# Display_Indicators.net
KiCad netlist of a schematic drawn in Altium Designer
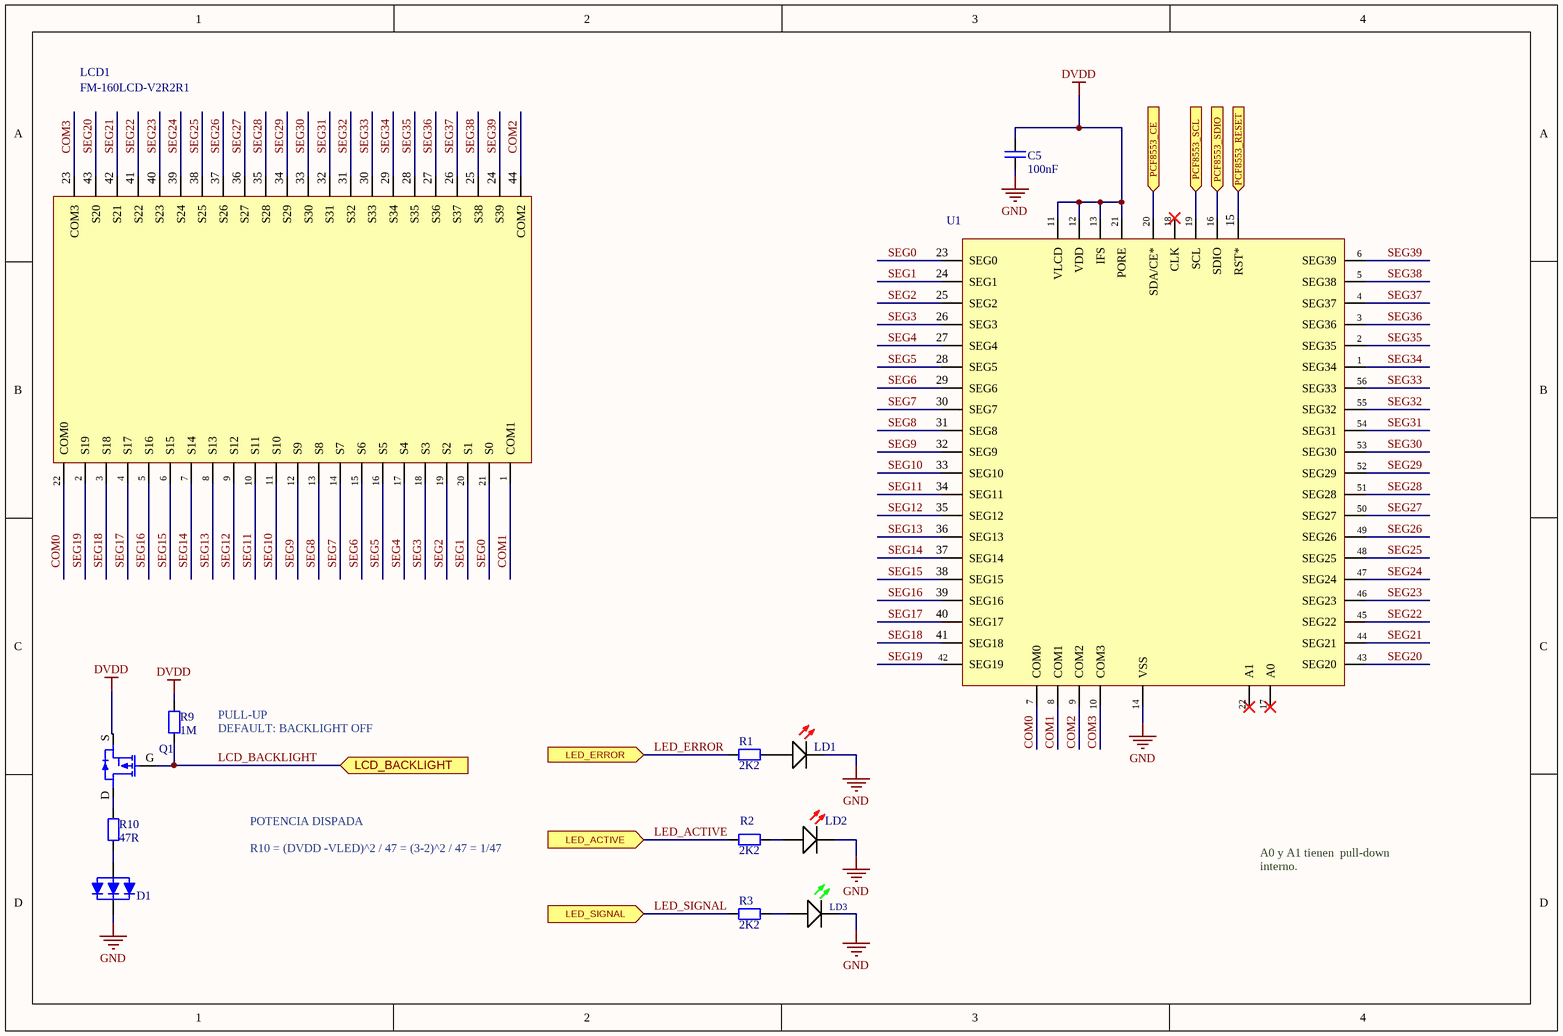
[diagram p0: Display_Indicators.SchDoc]

(export (version "E")
  (design (tool "Eeschema 10.0.6"))
  (components
    (comp (ref "C5")
      (value "100nF")
      (footprint "CAP_SM0603_YAGEOCC2_N")
      (description "CAP 100nF SM0603 X7R 50V YAGEO CC2")
      (fields
        (field (name "MANUFACTURER") "Yageo")
        (field (name "MANUFACTURER PART NUMBER") "CC0603KRX7R9BB104")
      )
      (libsource (lib "yageo") (part "CC0603KRX7R9BB104"))
    )
    (comp (ref "D1")
      (value "BACKLIGHT")
      (footprint "BACKLIGHT_2")
      (description "IF=45mA;VF=3V")
      (fields
        (field (name "MANUFACTURER") "FLOWMEET")
        (field (name "MANUFACTURER PART NUMBER") "FM-160-BACKLIGHT")
      )
      (libsource (lib "flowmeet") (part "FM-160-BACKLIGHT"))
    )
    (comp (ref "LCD1")
      (value "FM-160LCD-V2R2R1")
      (footprint "FMC-160LCD V2")
      (fields (field (name "MANUFACTURER") "FLOWMEET"))
      (libsource (lib "flowmeet") (part "FM-160LCD-V2R2R1"))
    )
    (comp (ref "LD1")
      (value "RED")
      (footprint "LED 0805")
      (fields
        (field (name "MANUFACTURER") "Everlight Elec")
        (field (name "MANUFACTURER PART NUMBER") "17-21SURC/S530-A2/TR8")
      )
      (libsource (lib "flowmeet") (part "17-21SURC/S530-A2/TR8"))
    )
    (comp (ref "LD2")
      (value "RED")
      (footprint "LED 0805")
      (fields
        (field (name "MANUFACTURER") "Everlight Elec")
        (field (name "MANUFACTURER PART NUMBER") "17-21SURC/S530-A2/TR8")
      )
      (libsource (lib "flowmeet") (part "17-21SURC/S530-A2/TR8"))
    )
    (comp (ref "LD3")
      (value "GREEN")
      (footprint "LED 0805")
      (fields
        (field (name "MANUFACTURER") "Everlight Elec")
        (field (name "MANUFACTURER PART NUMBER") "21SYGC/S530-E2/TR8")
      )
      (libsource (lib "flowmeet") (part "17-21SYGC/S530-E2/TR8"))
    )
    (comp (ref "Q1")
      (value "DMG3401LSN-7")
      (footprint "DMG3401LSN-7")
      (description "P-CHANNEL ENHANCEMENT MODE MOSFET\r\nRDS(ON) = 85mΩ @ VGS = -2.5V -> ID -2.7A\r\nV(BR)DDS 30V")
      (fields (field (name "MANUFACTURER") "Diodes Incorporated"))
      (libsource (lib "mosfet") (part "DMG3401LSN-7"))
    )
    (comp (ref "R1")
      (value "2K2")
      (footprint "RES_SM0603_YAGEORC_N")
      (description "RES 2K2 SM0603 YAGEO RC_L")
      (fields
        (field (name "MANUFACTURER") "Yageo")
        (field (name "MANUFACTURER PART NUMBER") "RC0603FR-072K2L")
      )
      (libsource (lib "yageo") (part "RC0603FR-072K2L"))
    )
    (comp (ref "R2")
      (value "2K2")
      (footprint "RES_SM0603_YAGEORC_N")
      (description "RES 2K2 SM0603 YAGEO RC_L")
      (fields
        (field (name "MANUFACTURER") "Yageo")
        (field (name "MANUFACTURER PART NUMBER") "RC0603FR-072K2L")
      )
      (libsource (lib "yageo") (part "RC0603FR-072K2L"))
    )
    (comp (ref "R3")
      (value "2K2")
      (footprint "RES_SM0603_YAGEORC_N")
      (description "RES 2K2 SM0603 YAGEO RC_L")
      (fields
        (field (name "MANUFACTURER") "Yageo")
        (field (name "MANUFACTURER PART NUMBER") "RC0603FR-072K2L")
      )
      (libsource (lib "yageo") (part "RC0603FR-072K2L"))
    )
    (comp (ref "R9")
      (value "1M")
      (footprint "RES_SM0603_YAGEORC_N")
      (description "RES 1M SM0603 YAGEO RC_L")
      (fields
        (field (name "MANUFACTURER") "Yageo")
        (field (name "MANUFACTURER PART NUMBER") "RC0603FR-071ML")
      )
      (libsource (lib "yageo") (part "RC0603FR-071ML"))
    )
    (comp (ref "R10")
      (value "47R")
      (footprint "RES_SM0603_YAGEORC_N")
      (description "RES 47R SM0603 YAGEO RC_L")
      (fields
        (field (name "MANUFACTURER") "Yageo")
        (field (name "MANUFACTURER PART NUMBER") "RC0603FR-0747RL")
      )
      (libsource (lib "yageo") (part "RC0603FR-0747RL"))
    )
    (comp (ref "U1")
      (value "~")
      (footprint "LCD DRIVER - TSSOP56")
      (description "40 × 4 LCD SEGMENT DRIVER")
      (fields (field (name "MANUFACTURER") "NXP") (field (name "MANUFACTURER PART NUMBER") "PCF8553DTT/AY"))
      (libsource (lib "flowmeet") (part "PCF8553DTT/AY"))
    )
  )
  (nets
    (net (code "1") (name "/COM0") (class "Default")
      (node (ref "LCD1") (pin "22") (pinfunction "COM0_22") (pintype "passive"))
      (node (ref "U1") (pin "7") (pinfunction "COM0_7") (pintype "passive"))
    )
    (net (code "2") (name "/COM1") (class "Default")
      (node (ref "LCD1") (pin "1") (pinfunction "COM1_1") (pintype "passive"))
      (node (ref "U1") (pin "8") (pinfunction "COM1_8") (pintype "passive"))
    )
    (net (code "3") (name "/COM2") (class "Default")
      (node (ref "LCD1") (pin "44") (pinfunction "COM2_44") (pintype "passive"))
      (node (ref "U1") (pin "9") (pinfunction "COM2_9") (pintype "passive"))
    )
    (net (code "4") (name "/COM3") (class "Default")
      (node (ref "LCD1") (pin "23") (pinfunction "COM3_23") (pintype "passive"))
      (node (ref "U1") (pin "10") (pinfunction "COM3_10") (pintype "passive"))
    )
    (net (code "5") (name "/LCD_BACKLIGHT") (class "Default")
      (node (ref "Q1") (pin "G") (pinfunction "G_G") (pintype "passive"))
      (node (ref "R9") (pin "1") (pintype "passive"))
    )
    (net (code "6") (name "/LED_ACTIVE") (class "Default") (node (ref "R2") (pin "1") (pintype "passive")))
    (net (code "7") (name "/LED_ERROR") (class "Default") (node (ref "R1") (pin "1") (pintype "passive")))
    (net (code "8") (name "/LED_SIGNAL") (class "Default") (node (ref "R3") (pin "1") (pintype "passive")))
    (net (code "9") (name "/PCF8553_CE") (class "Default")
      (node (ref "U1") (pin "20") (pinfunction "SDA/CE*_20") (pintype "passive"))
    )
    (net (code "10") (name "/PCF8553_RESET") (class "Default")
      (node (ref "U1") (pin "15") (pinfunction "RST*_15") (pintype "passive"))
    )
    (net (code "11") (name "/PCF8553_SCL") (class "Default")
      (node (ref "U1") (pin "19") (pinfunction "SCL_19") (pintype "passive"))
    )
    (net (code "12") (name "/PCF8553_SDIO") (class "Default")
      (node (ref "U1") (pin "16") (pinfunction "SDIO_16") (pintype "passive"))
    )
    (net (code "13") (name "/SEG0") (class "Default")
      (node (ref "LCD1") (pin "21") (pinfunction "S0_21") (pintype "passive"))
      (node (ref "U1") (pin "23") (pinfunction "SEG0_23") (pintype "passive"))
    )
    (net (code "14") (name "/SEG1") (class "Default")
      (node (ref "LCD1") (pin "20") (pinfunction "S1_20") (pintype "passive"))
      (node (ref "U1") (pin "24") (pinfunction "SEG1_24") (pintype "passive"))
    )
    (net (code "15") (name "/SEG2") (class "Default")
      (node (ref "LCD1") (pin "19") (pinfunction "S2_19") (pintype "passive"))
      (node (ref "U1") (pin "25") (pinfunction "SEG2_25") (pintype "passive"))
    )
    (net (code "16") (name "/SEG3") (class "Default")
      (node (ref "LCD1") (pin "18") (pinfunction "S3_18") (pintype "passive"))
      (node (ref "U1") (pin "26") (pinfunction "SEG3_26") (pintype "passive"))
    )
    (net (code "17") (name "/SEG4") (class "Default")
      (node (ref "LCD1") (pin "17") (pinfunction "S4_17") (pintype "passive"))
      (node (ref "U1") (pin "27") (pinfunction "SEG4_27") (pintype "passive"))
    )
    (net (code "18") (name "/SEG5") (class "Default")
      (node (ref "LCD1") (pin "16") (pinfunction "S5_16") (pintype "passive"))
      (node (ref "U1") (pin "28") (pinfunction "SEG5_28") (pintype "passive"))
    )
    (net (code "19") (name "/SEG6") (class "Default")
      (node (ref "LCD1") (pin "15") (pinfunction "S6_15") (pintype "passive"))
      (node (ref "U1") (pin "29") (pinfunction "SEG6_29") (pintype "passive"))
    )
    (net (code "20") (name "/SEG7") (class "Default")
      (node (ref "LCD1") (pin "14") (pinfunction "S7_14") (pintype "passive"))
      (node (ref "U1") (pin "30") (pinfunction "SEG7_30") (pintype "passive"))
    )
    (net (code "21") (name "/SEG8") (class "Default")
      (node (ref "LCD1") (pin "13") (pinfunction "S8_13") (pintype "passive"))
      (node (ref "U1") (pin "31") (pinfunction "SEG8_31") (pintype "passive"))
    )
    (net (code "22") (name "/SEG9") (class "Default")
      (node (ref "LCD1") (pin "12") (pinfunction "S9_12") (pintype "passive"))
      (node (ref "U1") (pin "32") (pinfunction "SEG9_32") (pintype "passive"))
    )
    (net (code "23") (name "/SEG10") (class "Default")
      (node (ref "LCD1") (pin "11") (pinfunction "S10_11") (pintype "passive"))
      (node (ref "U1") (pin "33") (pinfunction "SEG10_33") (pintype "passive"))
    )
    (net (code "24") (name "/SEG11") (class "Default")
      (node (ref "LCD1") (pin "10") (pinfunction "S11_10") (pintype "passive"))
      (node (ref "U1") (pin "34") (pinfunction "SEG11_34") (pintype "passive"))
    )
    (net (code "25") (name "/SEG12") (class "Default")
      (node (ref "LCD1") (pin "9") (pinfunction "S12_9") (pintype "passive"))
      (node (ref "U1") (pin "35") (pinfunction "SEG12_35") (pintype "passive"))
    )
    (net (code "26") (name "/SEG13") (class "Default")
      (node (ref "LCD1") (pin "8") (pinfunction "S13_8") (pintype "passive"))
      (node (ref "U1") (pin "36") (pinfunction "SEG13_36") (pintype "passive"))
    )
    (net (code "27") (name "/SEG14") (class "Default")
      (node (ref "LCD1") (pin "7") (pinfunction "S14_7") (pintype "passive"))
      (node (ref "U1") (pin "37") (pinfunction "SEG14_37") (pintype "passive"))
    )
    (net (code "28") (name "/SEG15") (class "Default")
      (node (ref "LCD1") (pin "6") (pinfunction "S15_6") (pintype "passive"))
      (node (ref "U1") (pin "38") (pinfunction "SEG15_38") (pintype "passive"))
    )
    (net (code "29") (name "/SEG16") (class "Default")
      (node (ref "LCD1") (pin "5") (pinfunction "S16_5") (pintype "passive"))
      (node (ref "U1") (pin "39") (pinfunction "SEG16_39") (pintype "passive"))
    )
    (net (code "30") (name "/SEG17") (class "Default")
      (node (ref "LCD1") (pin "4") (pinfunction "S17_4") (pintype "passive"))
      (node (ref "U1") (pin "40") (pinfunction "SEG17_40") (pintype "passive"))
    )
    (net (code "31") (name "/SEG18") (class "Default")
      (node (ref "LCD1") (pin "3") (pinfunction "S18_3") (pintype "passive"))
      (node (ref "U1") (pin "41") (pinfunction "SEG18_41") (pintype "passive"))
    )
    (net (code "32") (name "/SEG19") (class "Default")
      (node (ref "LCD1") (pin "2") (pinfunction "S19_2") (pintype "passive"))
      (node (ref "U1") (pin "42") (pinfunction "SEG19_42") (pintype "passive"))
    )
    (net (code "33") (name "/SEG20") (class "Default")
      (node (ref "LCD1") (pin "43") (pinfunction "S20_43") (pintype "passive"))
      (node (ref "U1") (pin "43") (pinfunction "SEG20_43") (pintype "passive"))
    )
    (net (code "34") (name "/SEG21") (class "Default")
      (node (ref "LCD1") (pin "42") (pinfunction "S21_42") (pintype "passive"))
      (node (ref "U1") (pin "44") (pinfunction "SEG21_44") (pintype "passive"))
    )
    (net (code "35") (name "/SEG22") (class "Default")
      (node (ref "LCD1") (pin "41") (pinfunction "S22_41") (pintype "passive"))
      (node (ref "U1") (pin "45") (pinfunction "SEG22_45") (pintype "passive"))
    )
    (net (code "36") (name "/SEG23") (class "Default")
      (node (ref "LCD1") (pin "40") (pinfunction "S23_40") (pintype "passive"))
      (node (ref "U1") (pin "46") (pinfunction "SEG23_46") (pintype "passive"))
    )
    (net (code "37") (name "/SEG24") (class "Default")
      (node (ref "LCD1") (pin "39") (pinfunction "S24_39") (pintype "passive"))
      (node (ref "U1") (pin "47") (pinfunction "SEG24_47") (pintype "passive"))
    )
    (net (code "38") (name "/SEG25") (class "Default")
      (node (ref "LCD1") (pin "38") (pinfunction "S25_38") (pintype "passive"))
      (node (ref "U1") (pin "48") (pinfunction "SEG25_48") (pintype "passive"))
    )
    (net (code "39") (name "/SEG26") (class "Default")
      (node (ref "LCD1") (pin "37") (pinfunction "S26_37") (pintype "passive"))
      (node (ref "U1") (pin "49") (pinfunction "SEG26_49") (pintype "passive"))
    )
    (net (code "40") (name "/SEG27") (class "Default")
      (node (ref "LCD1") (pin "36") (pinfunction "S27_36") (pintype "passive"))
      (node (ref "U1") (pin "50") (pinfunction "SEG27_50") (pintype "passive"))
    )
    (net (code "41") (name "/SEG28") (class "Default")
      (node (ref "LCD1") (pin "35") (pinfunction "S28_35") (pintype "passive"))
      (node (ref "U1") (pin "51") (pinfunction "SEG28_51") (pintype "passive"))
    )
    (net (code "42") (name "/SEG29") (class "Default")
      (node (ref "LCD1") (pin "34") (pinfunction "S29_34") (pintype "passive"))
      (node (ref "U1") (pin "52") (pinfunction "SEG29_52") (pintype "passive"))
    )
    (net (code "43") (name "/SEG30") (class "Default")
      (node (ref "LCD1") (pin "33") (pinfunction "S30_33") (pintype "passive"))
      (node (ref "U1") (pin "53") (pinfunction "SEG30_53") (pintype "passive"))
    )
    (net (code "44") (name "/SEG31") (class "Default")
      (node (ref "LCD1") (pin "32") (pinfunction "S31_32") (pintype "passive"))
      (node (ref "U1") (pin "54") (pinfunction "SEG31_54") (pintype "passive"))
    )
    (net (code "45") (name "/SEG32") (class "Default")
      (node (ref "LCD1") (pin "31") (pinfunction "S32_31") (pintype "passive"))
      (node (ref "U1") (pin "55") (pinfunction "SEG32_55") (pintype "passive"))
    )
    (net (code "46") (name "/SEG33") (class "Default")
      (node (ref "LCD1") (pin "30") (pinfunction "S33_30") (pintype "passive"))
      (node (ref "U1") (pin "56") (pinfunction "SEG33_56") (pintype "passive"))
    )
    (net (code "47") (name "/SEG34") (class "Default")
      (node (ref "LCD1") (pin "29") (pinfunction "S34_29") (pintype "passive"))
      (node (ref "U1") (pin "1") (pinfunction "SEG34_1") (pintype "passive"))
    )
    (net (code "48") (name "/SEG35") (class "Default")
      (node (ref "LCD1") (pin "28") (pinfunction "S35_28") (pintype "passive"))
      (node (ref "U1") (pin "2") (pinfunction "SEG35_2") (pintype "passive"))
    )
    (net (code "49") (name "/SEG36") (class "Default")
      (node (ref "LCD1") (pin "27") (pinfunction "S36_27") (pintype "passive"))
      (node (ref "U1") (pin "3") (pinfunction "SEG36_3") (pintype "passive"))
    )
    (net (code "50") (name "/SEG37") (class "Default")
      (node (ref "LCD1") (pin "26") (pinfunction "S37_26") (pintype "passive"))
      (node (ref "U1") (pin "4") (pinfunction "SEG37_4") (pintype "passive"))
    )
    (net (code "51") (name "/SEG38") (class "Default")
      (node (ref "LCD1") (pin "25") (pinfunction "S38_25") (pintype "passive"))
      (node (ref "U1") (pin "5") (pinfunction "SEG38_5") (pintype "passive"))
    )
    (net (code "52") (name "/SEG39") (class "Default")
      (node (ref "LCD1") (pin "24") (pinfunction "S39_24") (pintype "passive"))
      (node (ref "U1") (pin "6") (pinfunction "SEG39_6") (pintype "passive"))
    )
    (net (code "53") (name "DVDD") (class "Default")
      (node (ref "C5") (pin "1") (pintype "passive"))
      (node (ref "Q1") (pin "S") (pinfunction "S_S") (pintype "passive"))
      (node (ref "R9") (pin "2") (pintype "passive"))
      (node (ref "U1") (pin "11") (pinfunction "VLCD_11") (pintype "passive"))
      (node (ref "U1") (pin "12") (pinfunction "VDD_12") (pintype "passive"))
      (node (ref "U1") (pin "13") (pinfunction "IFS_13") (pintype "passive"))
      (node (ref "U1") (pin "21") (pinfunction "PORE_21") (pintype "passive"))
    )
    (net (code "54") (name "GND") (class "Default")
      (node (ref "C5") (pin "2") (pintype "passive"))
      (node (ref "D1") (pin "2") (pinfunction "0_2") (pintype "passive"))
      (node (ref "LD1") (pin "K") (pinfunction "K_K") (pintype "passive"))
      (node (ref "LD2") (pin "K") (pinfunction "K_K") (pintype "passive"))
      (node (ref "LD3") (pin "K") (pinfunction "K_K") (pintype "passive"))
      (node (ref "U1") (pin "14") (pinfunction "VSS_14") (pintype "passive"))
    )
    (net (code "55") (name "Net-(D1-Pad1)") (class "Default")
      (node (ref "D1") (pin "1") (pinfunction "1_1") (pintype "passive"))
      (node (ref "R10") (pin "1") (pintype "passive"))
    )
    (net (code "56") (name "Net-(LD1-PadA)") (class "Default")
      (node (ref "LD1") (pin "A") (pinfunction "A_A") (pintype "passive"))
      (node (ref "R1") (pin "2") (pintype "passive"))
    )
    (net (code "57") (name "Net-(LD2-PadA)") (class "Default")
      (node (ref "LD2") (pin "A") (pinfunction "A_A") (pintype "passive"))
      (node (ref "R2") (pin "2") (pintype "passive"))
    )
    (net (code "58") (name "Net-(LD3-PadA)") (class "Default")
      (node (ref "LD3") (pin "A") (pinfunction "A_A") (pintype "passive"))
      (node (ref "R3") (pin "2") (pintype "passive"))
    )
    (net (code "59") (name "Net-(Q1-PadD)") (class "Default")
      (node (ref "Q1") (pin "D") (pinfunction "D_D") (pintype "passive"))
      (node (ref "R10") (pin "2") (pintype "passive"))
    )
    (net (code "60") (name "unconnected-(U1-A0-Pad17)") (class "Default")
      (node (ref "U1") (pin "17") (pinfunction "A0_17") (pintype "passive+no_connect"))
    )
    (net (code "61") (name "unconnected-(U1-A1-Pad22)") (class "Default")
      (node (ref "U1") (pin "22") (pinfunction "A1_22") (pintype "passive+no_connect"))
    )
    (net (code "62") (name "unconnected-(U1-CLK-Pad18)") (class "Default")
      (node (ref "U1") (pin "18") (pinfunction "CLK_18") (pintype "passive+no_connect"))
    )
  )
)
